# SAO-232.net
KiCad netlist of a schematic drawn in EAGLE
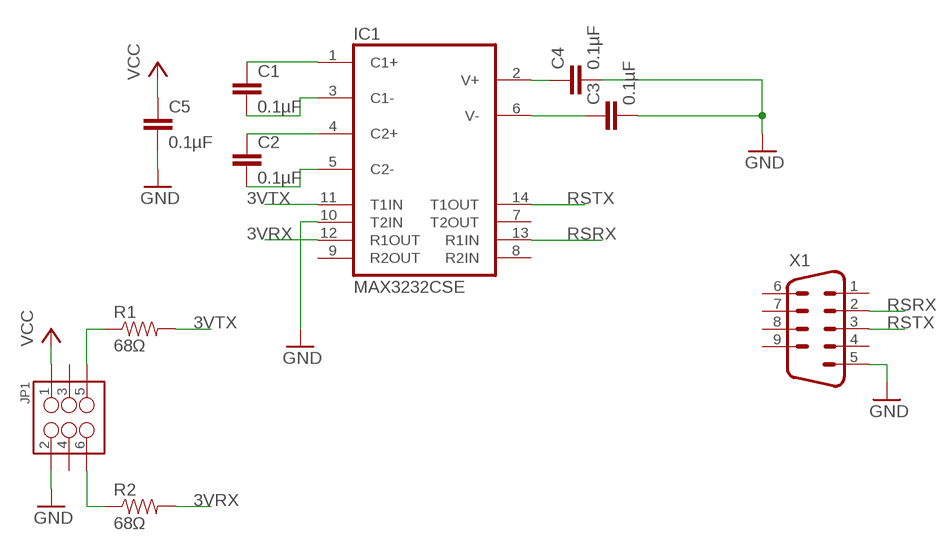
[diagram p0: schematic, sheet 1]

(export (version "E")
  (design (tool "Eeschema 10.0.6"))
  (components
    (comp (ref "C1")
      (value "0.1µF")
      (footprint "eagle-import:0805")
      (libsource (lib "eagle-import") (part "CAP0805"))
    )
    (comp (ref "C2")
      (value "0.1µF")
      (footprint "eagle-import:0805")
      (libsource (lib "eagle-import") (part "CAP0805"))
    )
    (comp (ref "C3")
      (value "0.1µF")
      (footprint "eagle-import:0805")
      (libsource (lib "eagle-import") (part "CAP0805"))
    )
    (comp (ref "C4")
      (value "0.1µF")
      (footprint "eagle-import:0805")
      (libsource (lib "eagle-import") (part "CAP0805"))
    )
    (comp (ref "C5")
      (value "0.1µF")
      (footprint "eagle-import:0805")
      (libsource (lib "eagle-import") (part "CAP0805"))
    )
    (comp (ref "IC1")
      (value "MAX3232CSE")
      (footprint "eagle-import:SO16")
      (libsource (lib "eagle-import") (part "MAX3232SEC"))
    )
    (comp (ref "JP1")
      (value "M03X2NO_SILK")
      (footprint "eagle-import:2X3-NS")
      (libsource (lib "eagle-import") (part "M03X2NO_SILK"))
    )
    (comp (ref "R1")
      (value "68Ω")
      (footprint "eagle-import:0805")
      (libsource (lib "eagle-import") (part "RESISTOR0805-RES"))
    )
    (comp (ref "R2")
      (value "68Ω")
      (footprint "eagle-import:0805")
      (libsource (lib "eagle-import") (part "RESISTOR0805-RES"))
    )
    (comp (ref "X1")
      (value "M09D")
      (footprint "eagle-import:M09D")
      (libsource (lib "eagle-import") (part "M09D"))
    )
  )
  (nets
    (net (code "1") (name "/3VRX") (class "Default")
      (node (ref "IC1") (pin "12") (pinfunction "R1OUT_12") (pintype "output"))
      (node (ref "R2") (pin "2") (pinfunction "2_2") (pintype "passive"))
    )
    (net (code "2") (name "/3VTX") (class "Default")
      (node (ref "IC1") (pin "11") (pinfunction "T1IN_11") (pintype "input"))
      (node (ref "R1") (pin "2") (pinfunction "2_2") (pintype "passive"))
    )
    (net (code "3") (name "/RSRX") (class "Default")
      (node (ref "IC1") (pin "13") (pinfunction "R1IN_13") (pintype "input"))
      (node (ref "X1") (pin "2") (pinfunction "2_2") (pintype "passive"))
    )
    (net (code "4") (name "/RSTX") (class "Default")
      (node (ref "IC1") (pin "14") (pinfunction "T1OUT_14") (pintype "output"))
      (node (ref "X1") (pin "3") (pinfunction "3_3") (pintype "passive"))
    )
    (net (code "5") (name "GND") (class "Default")
      (node (ref "C3") (pin "2") (pinfunction "2_2") (pintype "passive"))
      (node (ref "C4") (pin "2") (pinfunction "2_2") (pintype "passive"))
      (node (ref "C5") (pin "2") (pinfunction "2_2") (pintype "passive"))
      (node (ref "IC1") (pin "10") (pinfunction "T2IN_10") (pintype "input"))
      (node (ref "JP1") (pin "2") (pinfunction "2_2") (pintype "bidirectional"))
      (node (ref "X1") (pin "5") (pinfunction "5_5") (pintype "passive"))
    )
    (net (code "6") (name "Net-(IC1A-C1+)") (class "Default")
      (node (ref "C1") (pin "1") (pinfunction "1_1") (pintype "passive"))
      (node (ref "IC1") (pin "1") (pinfunction "C1+_1") (pintype "bidirectional"))
    )
    (net (code "7") (name "Net-(IC1A-C1-)") (class "Default")
      (node (ref "C1") (pin "2") (pinfunction "2_2") (pintype "passive"))
      (node (ref "IC1") (pin "3") (pinfunction "C1-_3") (pintype "bidirectional"))
    )
    (net (code "8") (name "Net-(IC1A-C2+)") (class "Default")
      (node (ref "C2") (pin "1") (pinfunction "1_1") (pintype "passive"))
      (node (ref "IC1") (pin "4") (pinfunction "C2+_4") (pintype "bidirectional"))
    )
    (net (code "9") (name "Net-(IC1A-C2-)") (class "Default")
      (node (ref "C2") (pin "2") (pinfunction "2_2") (pintype "passive"))
      (node (ref "IC1") (pin "5") (pinfunction "C2-_5") (pintype "bidirectional"))
    )
    (net (code "10") (name "Net-(IC1A-V+)") (class "Default")
      (node (ref "C4") (pin "1") (pinfunction "1_1") (pintype "passive"))
      (node (ref "IC1") (pin "2") (pinfunction "V+_2") (pintype "bidirectional"))
    )
    (net (code "11") (name "Net-(IC1A-V-)") (class "Default")
      (node (ref "C3") (pin "1") (pinfunction "1_1") (pintype "passive"))
      (node (ref "IC1") (pin "6") (pinfunction "V-_6") (pintype "bidirectional"))
    )
    (net (code "12") (name "Net-(JP1-Pad5)") (class "Default")
      (node (ref "JP1") (pin "5") (pinfunction "5_5") (pintype "bidirectional"))
      (node (ref "R1") (pin "1") (pinfunction "1_1") (pintype "passive"))
    )
    (net (code "13") (name "Net-(JP1-Pad6)") (class "Default")
      (node (ref "JP1") (pin "6") (pinfunction "6_6") (pintype "bidirectional"))
      (node (ref "R2") (pin "1") (pinfunction "1_1") (pintype "passive"))
    )
    (net (code "14") (name "VCC") (class "Default")
      (node (ref "C5") (pin "1") (pinfunction "1_1") (pintype "passive"))
      (node (ref "JP1") (pin "1") (pinfunction "1_1") (pintype "bidirectional"))
    )
    (net (code "15") (name "unconnected-(IC1A-R2IN-Pad8)") (class "Default")
      (node (ref "IC1") (pin "8") (pinfunction "R2IN_8") (pintype "input"))
    )
    (net (code "16") (name "unconnected-(IC1A-R2OUT-Pad9)") (class "Default")
      (node (ref "IC1") (pin "9") (pinfunction "R2OUT_9") (pintype "output"))
    )
    (net (code "17") (name "unconnected-(IC1A-T2OUT-Pad7)") (class "Default")
      (node (ref "IC1") (pin "7") (pinfunction "T2OUT_7") (pintype "output"))
    )
    (net (code "18") (name "unconnected-(JP1-Pad3)") (class "Default")
      (node (ref "JP1") (pin "3") (pinfunction "3_3") (pintype "bidirectional"))
    )
    (net (code "19") (name "unconnected-(JP1-Pad4)") (class "Default")
      (node (ref "JP1") (pin "4") (pinfunction "4_4") (pintype "bidirectional"))
    )
    (net (code "20") (name "unconnected-(X1-Pad1)") (class "Default")
      (node (ref "X1") (pin "1") (pinfunction "1_1") (pintype "passive"))
    )
    (net (code "21") (name "unconnected-(X1-Pad4)") (class "Default")
      (node (ref "X1") (pin "4") (pinfunction "4_4") (pintype "passive"))
    )
    (net (code "22") (name "unconnected-(X1-Pad6)") (class "Default")
      (node (ref "X1") (pin "6") (pinfunction "6_6") (pintype "passive"))
    )
    (net (code "23") (name "unconnected-(X1-Pad7)") (class "Default")
      (node (ref "X1") (pin "7") (pinfunction "7_7") (pintype "passive"))
    )
    (net (code "24") (name "unconnected-(X1-Pad8)") (class "Default")
      (node (ref "X1") (pin "8") (pinfunction "8_8") (pintype "passive"))
    )
    (net (code "25") (name "unconnected-(X1-Pad9)") (class "Default")
      (node (ref "X1") (pin "9") (pinfunction "9_9") (pintype "passive"))
    )
  )
)
